# HUB_Sheet1.net
KiCad netlist of a schematic drawn in Altium Designer
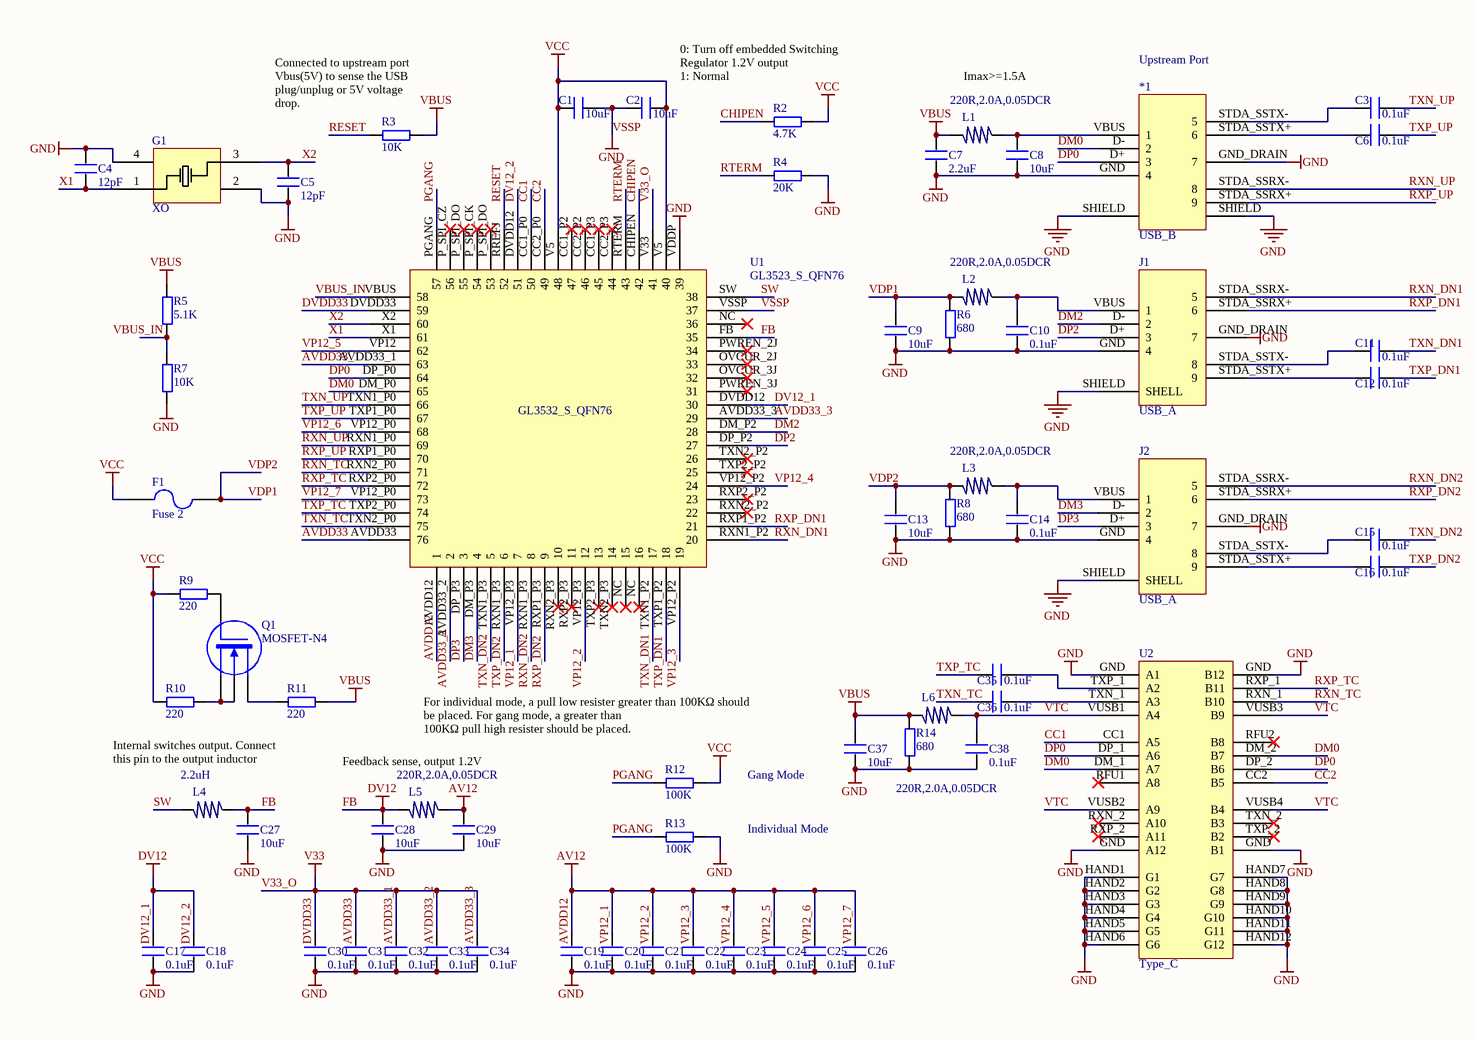
[diagram p0: HUB_Sheet1.SchDoc]

(export (version "E")
  (design (tool "Eeschema 10.0.6"))
  (components
    (comp (ref "*1")
      (value "USB_B")
      (footprint "USB3.0_TP")
      (description "USB3.0_B")
      (libsource (lib "HUB_GL3532") (part "USB_B"))
    )
    (comp (ref "C1") (value "10uF") (footprint "0603P") (libsource (lib "Explorer STM32F407封装库") (part "C")))
    (comp (ref "C2") (value "10uF") (footprint "0603P") (libsource (lib "Explorer STM32F407封装库") (part "C")))
    (comp (ref "C3") (value "0.1uF") (footprint "0603P") (libsource (lib "Explorer STM32F407封装库") (part "C")))
    (comp (ref "C4") (value "12pF") (footprint "0603P") (libsource (lib "Explorer STM32F407封装库") (part "C")))
    (comp (ref "C5") (value "12pF") (footprint "0603P") (libsource (lib "Explorer STM32F407封装库") (part "C")))
    (comp (ref "C6") (value "0.1uF") (footprint "0603P") (libsource (lib "Explorer STM32F407封装库") (part "C")))
    (comp (ref "C7") (value "2.2uF") (footprint "0603P") (libsource (lib "Explorer STM32F407封装库") (part "C")))
    (comp (ref "C8") (value "10uF") (footprint "0603P") (libsource (lib "Explorer STM32F407封装库") (part "C")))
    (comp (ref "C9") (value "10uF") (footprint "0603P") (libsource (lib "Explorer STM32F407封装库") (part "C")))
    (comp (ref "C10")
      (value "0.1uF")
      (footprint "0603P")
      (libsource (lib "Explorer STM32F407封装库") (part "C"))
    )
    (comp (ref "C11")
      (value "0.1uF")
      (footprint "0603P")
      (libsource (lib "Explorer STM32F407封装库") (part "C"))
    )
    (comp (ref "C12")
      (value "0.1uF")
      (footprint "0603P")
      (libsource (lib "Explorer STM32F407封装库") (part "C"))
    )
    (comp (ref "C13") (value "10uF") (footprint "0603P") (libsource (lib "Explorer STM32F407封装库") (part "C")))
    (comp (ref "C14")
      (value "0.1uF")
      (footprint "0603P")
      (libsource (lib "Explorer STM32F407封装库") (part "C"))
    )
    (comp (ref "C15")
      (value "0.1uF")
      (footprint "0603P")
      (libsource (lib "Explorer STM32F407封装库") (part "C"))
    )
    (comp (ref "C16")
      (value "0.1uF")
      (footprint "0603P")
      (libsource (lib "Explorer STM32F407封装库") (part "C"))
    )
    (comp (ref "C17")
      (value "0.1uF")
      (footprint "0603P")
      (libsource (lib "Explorer STM32F407封装库") (part "C"))
    )
    (comp (ref "C18")
      (value "0.1uF")
      (footprint "0603P")
      (libsource (lib "Explorer STM32F407封装库") (part "C"))
    )
    (comp (ref "C19")
      (value "0.1uF")
      (footprint "0603P")
      (libsource (lib "Explorer STM32F407封装库") (part "C"))
    )
    (comp (ref "C20")
      (value "0.1uF")
      (footprint "0603P")
      (libsource (lib "Explorer STM32F407封装库") (part "C"))
    )
    (comp (ref "C21")
      (value "0.1uF")
      (footprint "0603P")
      (libsource (lib "Explorer STM32F407封装库") (part "C"))
    )
    (comp (ref "C22")
      (value "0.1uF")
      (footprint "0603P")
      (libsource (lib "Explorer STM32F407封装库") (part "C"))
    )
    (comp (ref "C23")
      (value "0.1uF")
      (footprint "0603P")
      (libsource (lib "Explorer STM32F407封装库") (part "C"))
    )
    (comp (ref "C24")
      (value "0.1uF")
      (footprint "0603P")
      (libsource (lib "Explorer STM32F407封装库") (part "C"))
    )
    (comp (ref "C25")
      (value "0.1uF")
      (footprint "0603P")
      (libsource (lib "Explorer STM32F407封装库") (part "C"))
    )
    (comp (ref "C26")
      (value "0.1uF")
      (footprint "0603P")
      (libsource (lib "Explorer STM32F407封装库") (part "C"))
    )
    (comp (ref "C27") (value "10uF") (footprint "0603P") (libsource (lib "Explorer STM32F407封装库") (part "C")))
    (comp (ref "C28") (value "10uF") (footprint "0603P") (libsource (lib "Explorer STM32F407封装库") (part "C")))
    (comp (ref "C29") (value "10uF") (footprint "0603P") (libsource (lib "Explorer STM32F407封装库") (part "C")))
    (comp (ref "C30")
      (value "0.1uF")
      (footprint "0603P")
      (libsource (lib "Explorer STM32F407封装库") (part "C"))
    )
    (comp (ref "C31")
      (value "0.1uF")
      (footprint "0603P")
      (libsource (lib "Explorer STM32F407封装库") (part "C"))
    )
    (comp (ref "C32")
      (value "0.1uF")
      (footprint "0603P")
      (libsource (lib "Explorer STM32F407封装库") (part "C"))
    )
    (comp (ref "C33")
      (value "0.1uF")
      (footprint "0603P")
      (libsource (lib "Explorer STM32F407封装库") (part "C"))
    )
    (comp (ref "C34")
      (value "0.1uF")
      (footprint "0603P")
      (libsource (lib "Explorer STM32F407封装库") (part "C"))
    )
    (comp (ref "C35")
      (value "0.1uF")
      (footprint "0603P")
      (libsource (lib "Explorer STM32F407封装库") (part "C"))
    )
    (comp (ref "C36")
      (value "0.1uF")
      (footprint "0603P")
      (libsource (lib "Explorer STM32F407封装库") (part "C"))
    )
    (comp (ref "C37") (value "10uF") (footprint "0603P") (libsource (lib "Explorer STM32F407封装库") (part "C")))
    (comp (ref "C38")
      (value "0.1uF")
      (footprint "0603P")
      (libsource (lib "Explorer STM32F407封装库") (part "C"))
    )
    (comp (ref "F1")
      (value "Fuse 2")
      (footprint "PIN-W2/E2.8")
      (description "Fuse")
      (fields (field (name "PUBLISHER") "Altium Limited"))
      (libsource (lib "Miscellaneous Devices") (part "Fuse 2"))
    )
    (comp (ref "G1")
      (value "XO")
      (footprint "XTAL")
      (description "25M XO")
      (libsource (lib "HUB_GL3532") (part "XO"))
    )
    (comp (ref "J1") (value "USB_A") (description "USB3.0-A") (libsource (lib "GL3532") (part "USB_A")))
    (comp (ref "J2") (value "USB_A") (description "USB3.0-A") (libsource (lib "GL3532") (part "USB_A")))
    (comp (ref "L1")
      (value "220R,2.0A,0.05DCR")
      (footprint "0603P")
      (libsource (lib "Explorer STM32F407封装库") (part "L"))
    )
    (comp (ref "L2")
      (value "220R,2.0A,0.05DCR")
      (footprint "0603P")
      (libsource (lib "Explorer STM32F407封装库") (part "L"))
    )
    (comp (ref "L3")
      (value "220R,2.0A,0.05DCR")
      (footprint "0603P")
      (libsource (lib "Explorer STM32F407封装库") (part "L"))
    )
    (comp (ref "L4") (value "2.2uH") (footprint "0603P") (libsource (lib "Explorer STM32F407封装库") (part "L")))
    (comp (ref "L5")
      (value "220R,2.0A,0.05DCR")
      (footprint "0603P")
      (libsource (lib "Explorer STM32F407封装库") (part "L"))
    )
    (comp (ref "L6")
      (value "220R,2.0A,0.05DCR")
      (footprint "0603P")
      (libsource (lib "Explorer STM32F407封装库") (part "L"))
    )
    (comp (ref "Q1")
      (value "MOSFET-N4")
      (footprint "SOT-343_N")
      (description "N-Channel MOSFET, Externally Terminated Substrate")
      (fields (field (name "PUBLISHER") "Altium Limited"))
      (libsource (lib "Miscellaneous Devices") (part "MOSFET-N4"))
    )
    (comp (ref "R2") (value "4.7K") (footprint "0603P") (libsource (lib "Explorer STM32F407封装库") (part "R")))
    (comp (ref "R3") (value "10K") (footprint "0603P") (libsource (lib "Explorer STM32F407封装库") (part "R")))
    (comp (ref "R4") (value "20K") (footprint "0603P") (libsource (lib "Explorer STM32F407封装库") (part "R")))
    (comp (ref "R5") (value "5.1K") (footprint "0603P") (libsource (lib "Explorer STM32F407封装库") (part "R")))
    (comp (ref "R6") (value "680") (footprint "0603P") (libsource (lib "Explorer STM32F407封装库") (part "R")))
    (comp (ref "R7") (value "10K") (footprint "0603P") (libsource (lib "Explorer STM32F407封装库") (part "R")))
    (comp (ref "R8") (value "680") (footprint "0603P") (libsource (lib "Explorer STM32F407封装库") (part "R")))
    (comp (ref "R9") (value "220") (footprint "0603P") (libsource (lib "Explorer STM32F407封装库") (part "R")))
    (comp (ref "R10") (value "220") (footprint "0603P") (libsource (lib "Explorer STM32F407封装库") (part "R")))
    (comp (ref "R11") (value "220") (footprint "0603P") (libsource (lib "Explorer STM32F407封装库") (part "R")))
    (comp (ref "R12") (value "100K") (footprint "0603P") (libsource (lib "Explorer STM32F407封装库") (part "R")))
    (comp (ref "R13") (value "100K") (footprint "0603P") (libsource (lib "Explorer STM32F407封装库") (part "R")))
    (comp (ref "R14") (value "680") (footprint "0603P") (libsource (lib "Explorer STM32F407封装库") (part "R")))
    (comp (ref "U1") (value "GL3523_S_QFN76") (libsource (lib "GL3532") (part "GL3523_S_QFN76")))
    (comp (ref "U2") (value "Type_C") (libsource (lib "GL3532") (part "Type_C")))
  )
  (nets
    (net (code "1") (name "/AVDD12") (class "Default")
      (node (ref "U1") (pin "AVDD12") (pinfunction "1_AVDD12") (pintype "passive"))
    )
    (net (code "2") (name "/AVDD33") (class "Default")
      (node (ref "U1") (pin "AVDD33") (pinfunction "76_AVDD33") (pintype "passive"))
    )
    (net (code "3") (name "/AVDD33_1") (class "Default")
      (node (ref "U1") (pin "AVDD33_1") (pinfunction "63_AVDD33_1") (pintype "passive"))
    )
    (net (code "5") (name "/AVDD33_3") (class "Default")
      (node (ref "U1") (pin "AVDD33_3") (pinfunction "29_AVDD33_3") (pintype "passive"))
    )
    (net (code "6") (name "/CC1") (class "Default")
      (node (ref "U1") (pin "CC1_P0") (pinfunction "50_CC1_P0") (pintype "passive"))
      (node (ref "U2") (pin "CC1") (pinfunction "A5_CC1") (pintype "passive"))
    )
    (net (code "7") (name "/CC2") (class "Default")
      (node (ref "U1") (pin "CC2_P0") (pinfunction "49_CC2_P0") (pintype "passive"))
      (node (ref "U2") (pin "CC2") (pinfunction "B5_CC2") (pintype "passive"))
    )
    (net (code "8") (name "/CHIPEN") (class "Default")
      (node (ref "R2") (pin "1") (pintype "passive"))
      (node (ref "U1") (pin "CHIPEN") (pinfunction "42_CHIPEN") (pintype "passive"))
    )
    (net (code "9") (name "/DM0") (class "Default")
      (node (ref "*1") (pin "D-") (pinfunction "2_D-") (pintype "passive"))
      (node (ref "U1") (pin "DM_P0") (pinfunction "65_DM_P0") (pintype "passive"))
      (node (ref "U2") (pin "DM_1") (pinfunction "A7_DM_1") (pintype "passive"))
      (node (ref "U2") (pin "DM_2") (pinfunction "B7_DM_2") (pintype "passive"))
    )
    (net (code "10") (name "/DM2") (class "Default")
      (node (ref "J1") (pin "D-") (pinfunction "2_D-") (pintype "passive"))
      (node (ref "U1") (pin "DM_P2") (pinfunction "28_DM_P2") (pintype "passive"))
    )
    (net (code "11") (name "/DM3") (class "Default")
      (node (ref "J2") (pin "D-") (pinfunction "2_D-") (pintype "passive"))
      (node (ref "U1") (pin "DM_P3") (pinfunction "4_DM_P3") (pintype "passive"))
    )
    (net (code "12") (name "/DP0") (class "Default")
      (node (ref "*1") (pin "D+") (pinfunction "3_D+") (pintype "passive"))
      (node (ref "U1") (pin "DP_P0") (pinfunction "64_DP_P0") (pintype "passive"))
      (node (ref "U2") (pin "DP_1") (pinfunction "A6_DP_1") (pintype "passive"))
      (node (ref "U2") (pin "DP_2") (pinfunction "B6_DP_2") (pintype "passive"))
    )
    (net (code "13") (name "/DP2") (class "Default")
      (node (ref "J1") (pin "D+") (pinfunction "3_D+") (pintype "passive"))
      (node (ref "U1") (pin "DP_P2") (pinfunction "27_DP_P2") (pintype "passive"))
    )
    (net (code "14") (name "/DP3") (class "Default")
      (node (ref "J2") (pin "D+") (pinfunction "3_D+") (pintype "passive"))
      (node (ref "U1") (pin "DP_P3") (pinfunction "3_DP_P3") (pintype "passive"))
    )
    (net (code "15") (name "/DV12_1") (class "Default")
      (node (ref "U1") (pin "DVDD12") (pinfunction "30_DVDD12") (pintype "passive"))
    )
    (net (code "16") (name "/DV12_2") (class "Default")
      (node (ref "U1") (pin "DVDD12") (pinfunction "51_DVDD12") (pintype "passive"))
    )
    (net (code "17") (name "/DVDD33") (class "Default")
      (node (ref "U1") (pin "DVDD33") (pinfunction "59_DVDD33") (pintype "passive"))
    )
    (net (code "18") (name "/PGANG") (class "Default")
      (node (ref "R12") (pin "1") (pintype "passive"))
      (node (ref "R13") (pin "1") (pintype "passive"))
      (node (ref "U1") (pin "PGANG") (pinfunction "57_PGANG") (pintype "passive"))
    )
    (net (code "19") (name "/RESET") (class "Default")
      (node (ref "R3") (pin "1") (pintype "passive"))
      (node (ref "U1") (pin "RREFJ") (pinfunction "52_RREFJ") (pintype "passive"))
    )
    (net (code "20") (name "/RTERM") (class "Default")
      (node (ref "R4") (pin "1") (pintype "passive"))
      (node (ref "U1") (pin "RTERM") (pinfunction "43_RTERM") (pintype "passive"))
    )
    (net (code "21") (name "/RXN_DN1") (class "Default")
      (node (ref "J1") (pin "STDA_SSRX-") (pinfunction "5_STDA_SSRX-") (pintype "passive"))
      (node (ref "U1") (pin "RXN1_P2") (pinfunction "20_RXN1_P2") (pintype "passive"))
    )
    (net (code "22") (name "/RXN_DN2") (class "Default")
      (node (ref "J2") (pin "STDA_SSRX-") (pinfunction "5_STDA_SSRX-") (pintype "passive"))
    )
    (net (code "23") (name "/RXN_TC") (class "Default")
      (node (ref "U1") (pin "RXN2_P0") (pinfunction "71_RXN2_P0") (pintype "passive"))
      (node (ref "U2") (pin "RXN_1") (pinfunction "B10_RXN_1") (pintype "passive"))
    )
    (net (code "24") (name "/RXN_UP") (class "Default")
      (node (ref "*1") (pin "STDA_SSRX-") (pinfunction "8_STDA_SSRX-") (pintype "passive"))
      (node (ref "U1") (pin "RXN1_P0") (pinfunction "69_RXN1_P0") (pintype "passive"))
    )
    (net (code "25") (name "/RXP_DN1") (class "Default")
      (node (ref "J1") (pin "STDA_SSRX+") (pinfunction "6_STDA_SSRX+") (pintype "passive"))
      (node (ref "U1") (pin "RXP1_P2") (pinfunction "21_RXP1_P2") (pintype "passive"))
    )
    (net (code "26") (name "/RXP_DN2") (class "Default")
      (node (ref "J2") (pin "STDA_SSRX+") (pinfunction "6_STDA_SSRX+") (pintype "passive"))
    )
    (net (code "27") (name "/RXP_TC") (class "Default")
      (node (ref "U1") (pin "RXP2_P0") (pinfunction "72_RXP2_P0") (pintype "passive"))
      (node (ref "U2") (pin "RXP_1") (pinfunction "B11_RXP_1") (pintype "passive"))
    )
    (net (code "28") (name "/RXP_UP") (class "Default")
      (node (ref "*1") (pin "STDA_SSRX+") (pinfunction "9_STDA_SSRX+") (pintype "passive"))
      (node (ref "U1") (pin "RXP1_P0") (pinfunction "70_RXP1_P0") (pintype "passive"))
    )
    (net (code "29") (name "/SW") (class "Default")
      (node (ref "L4") (pin "2") (pintype "passive"))
      (node (ref "U1") (pin "SW") (pinfunction "38_SW") (pintype "passive"))
    )
    (net (code "30") (name "/TXN_DN1") (class "Default") (node (ref "C11") (pin "2") (pintype "passive")))
    (net (code "31") (name "/TXN_DN2") (class "Default") (node (ref "C15") (pin "2") (pintype "passive")))
    (net (code "32") (name "/TXN_TC") (class "Default")
      (node (ref "C36") (pin "1") (pintype "passive"))
      (node (ref "U1") (pin "TXN2_P0") (pinfunction "75_TXN2_P0") (pintype "passive"))
    )
    (net (code "33") (name "/TXN_UP") (class "Default")
      (node (ref "C3") (pin "2") (pintype "passive"))
      (node (ref "U1") (pin "TXN1_P0") (pinfunction "66_TXN1_P0") (pintype "passive"))
    )
    (net (code "34") (name "/TXP_DN1") (class "Default") (node (ref "C12") (pin "2") (pintype "passive")))
    (net (code "35") (name "/TXP_DN2") (class "Default") (node (ref "C16") (pin "2") (pintype "passive")))
    (net (code "36") (name "/TXP_TC") (class "Default")
      (node (ref "C35") (pin "1") (pintype "passive"))
      (node (ref "U1") (pin "TXP2_P0") (pinfunction "74_TXP2_P0") (pintype "passive"))
    )
    (net (code "37") (name "/TXP_UP") (class "Default")
      (node (ref "C6") (pin "2") (pintype "passive"))
      (node (ref "U1") (pin "TXP1_P0") (pinfunction "67_TXP1_P0") (pintype "passive"))
    )
    (net (code "38") (name "/VBUS_IN") (class "Default")
      (node (ref "U1") (pin "VBUS") (pinfunction "58_VBUS") (pintype "passive"))
    )
    (net (code "39") (name "/VDP1") (class "Default")
      (node (ref "C13") (pin "2") (pintype "passive"))
      (node (ref "C9") (pin "2") (pintype "passive"))
      (node (ref "F1") (pin "2") (pinfunction "2_2") (pintype "passive"))
      (node (ref "L2") (pin "2") (pintype "passive"))
      (node (ref "L3") (pin "2") (pintype "passive"))
      (node (ref "R6") (pin "2") (pintype "passive"))
      (node (ref "R8") (pin "2") (pintype "passive"))
    )
    (net (code "43") (name "/VP12_4") (class "Default")
      (node (ref "U1") (pin "VP12_P2") (pinfunction "24_VP12_P2") (pintype "passive"))
    )
    (net (code "44") (name "/VP12_5") (class "Default")
      (node (ref "U1") (pin "VP12") (pinfunction "62_VP12") (pintype "passive"))
    )
    (net (code "45") (name "/VP12_6") (class "Default")
      (node (ref "U1") (pin "VP12_P0") (pinfunction "68_VP12_P0") (pintype "passive"))
    )
    (net (code "46") (name "/VP12_7") (class "Default")
      (node (ref "U1") (pin "VP12_P0") (pinfunction "73_VP12_P0") (pintype "passive"))
    )
    (net (code "47") (name "/VTC") (class "Default")
      (node (ref "C38") (pin "2") (pintype "passive"))
      (node (ref "L6") (pin "1") (pintype "passive"))
      (node (ref "U2") (pin "VUSB1") (pinfunction "A4_VUSB1") (pintype "passive"))
      (node (ref "U2") (pin "VUSB2") (pinfunction "A9_VUSB2") (pintype "passive"))
      (node (ref "U2") (pin "VUSB3") (pinfunction "B9_VUSB3") (pintype "passive"))
      (node (ref "U2") (pin "VUSB4") (pinfunction "B4_VUSB4") (pintype "passive"))
    )
    (net (code "48") (name "/X1") (class "Default")
      (node (ref "C4") (pin "1") (pintype "passive"))
      (node (ref "G1") (pin "1") (pintype "passive"))
      (node (ref "U1") (pin "X1") (pinfunction "61_X1") (pintype "passive"))
    )
    (net (code "49") (name "/X2") (class "Default")
      (node (ref "C5") (pin "2") (pintype "passive"))
      (node (ref "G1") (pin "3") (pintype "passive"))
      (node (ref "U1") (pin "X2") (pinfunction "60_X2") (pintype "passive"))
    )
    (net (code "50") (name "AV12") (class "Default")
      (node (ref "C19") (pin "2") (pintype "passive"))
      (node (ref "C20") (pin "2") (pintype "passive"))
      (node (ref "C21") (pin "2") (pintype "passive"))
      (node (ref "C22") (pin "2") (pintype "passive"))
      (node (ref "C23") (pin "2") (pintype "passive"))
      (node (ref "C24") (pin "2") (pintype "passive"))
      (node (ref "C25") (pin "2") (pintype "passive"))
      (node (ref "C26") (pin "2") (pintype "passive"))
      (node (ref "C29") (pin "2") (pintype "passive"))
      (node (ref "L5") (pin "1") (pintype "passive"))
    )
    (net (code "51") (name "DV12") (class "Default")
      (node (ref "C17") (pin "2") (pintype "passive"))
      (node (ref "C18") (pin "2") (pintype "passive"))
      (node (ref "C27") (pin "2") (pintype "passive"))
      (node (ref "C28") (pin "2") (pintype "passive"))
      (node (ref "L4") (pin "1") (pintype "passive"))
      (node (ref "L5") (pin "2") (pintype "passive"))
      (node (ref "U1") (pin "FB") (pinfunction "35_FB") (pintype "passive"))
    )
    (net (code "52") (name "GND") (class "Default")
      (node (ref "*1") (pin "GND") (pinfunction "4_GND") (pintype "passive"))
      (node (ref "*1") (pin "GND_DRAIN") (pinfunction "7_GND_DRAIN") (pintype "passive"))
      (node (ref "*1") (pin "SHIELD") (pintype "passive"))
      (node (ref "C1") (pin "2") (pintype "passive"))
      (node (ref "C10") (pin "1") (pintype "passive"))
      (node (ref "C13") (pin "1") (pintype "passive"))
      (node (ref "C14") (pin "1") (pintype "passive"))
      (node (ref "C17") (pin "1") (pintype "passive"))
      (node (ref "C18") (pin "1") (pintype "passive"))
      (node (ref "C19") (pin "1") (pintype "passive"))
      (node (ref "C2") (pin "1") (pintype "passive"))
      (node (ref "C20") (pin "1") (pintype "passive"))
      (node (ref "C21") (pin "1") (pintype "passive"))
      (node (ref "C22") (pin "1") (pintype "passive"))
      (node (ref "C23") (pin "1") (pintype "passive"))
      (node (ref "C24") (pin "1") (pintype "passive"))
      (node (ref "C25") (pin "1") (pintype "passive"))
      (node (ref "C26") (pin "1") (pintype "passive"))
      (node (ref "C27") (pin "1") (pintype "passive"))
      (node (ref "C28") (pin "1") (pintype "passive"))
      (node (ref "C29") (pin "1") (pintype "passive"))
      (node (ref "C30") (pin "1") (pintype "passive"))
      (node (ref "C31") (pin "1") (pintype "passive"))
      (node (ref "C32") (pin "1") (pintype "passive"))
      (node (ref "C33") (pin "1") (pintype "passive"))
      (node (ref "C34") (pin "1") (pintype "passive"))
      (node (ref "C37") (pin "1") (pintype "passive"))
      (node (ref "C38") (pin "1") (pintype "passive"))
      (node (ref "C4") (pin "2") (pintype "passive"))
      (node (ref "C5") (pin "1") (pintype "passive"))
      (node (ref "C7") (pin "1") (pintype "passive"))
      (node (ref "C8") (pin "1") (pintype "passive"))
      (node (ref "C9") (pin "1") (pintype "passive"))
      (node (ref "G1") (pin "2") (pintype "passive"))
      (node (ref "G1") (pin "4") (pintype "passive"))
      (node (ref "J1") (pin "GND") (pinfunction "4_GND") (pintype "passive"))
      (node (ref "J1") (pin "GND_DRAIN") (pinfunction "7_GND_DRAIN") (pintype "passive"))
      (node (ref "J1") (pin "SHIELD") (pinfunction "SHELL_SHIELD") (pintype "passive"))
      (node (ref "J2") (pin "GND") (pinfunction "4_GND") (pintype "passive"))
      (node (ref "J2") (pin "GND_DRAIN") (pinfunction "7_GND_DRAIN") (pintype "passive"))
      (node (ref "J2") (pin "SHIELD") (pinfunction "SHELL_SHIELD") (pintype "passive"))
      (node (ref "R13") (pin "2") (pintype "passive"))
      (node (ref "R14") (pin "1") (pintype "passive"))
      (node (ref "R4") (pin "2") (pintype "passive"))
      (node (ref "R6") (pin "1") (pintype "passive"))
      (node (ref "R7") (pin "1") (pintype "passive"))
      (node (ref "R8") (pin "1") (pintype "passive"))
      (node (ref "U1") (pin "VDDP") (pinfunction "39_VDDP") (pintype "passive"))
      (node (ref "U1") (pin "VSSP") (pinfunction "37_VSSP") (pintype "passive"))
      (node (ref "U2") (pin "GND") (pinfunction "B12_GND") (pintype "passive"))
      (node (ref "U2") (pin "HAND1") (pinfunction "G1_HAND1") (pintype "passive"))
      (node (ref "U2") (pin "HAND10") (pinfunction "G10_HAND10") (pintype "passive"))
      (node (ref "U2") (pin "HAND11") (pinfunction "G11_HAND11") (pintype "passive"))
      (node (ref "U2") (pin "HAND12") (pinfunction "G12_HAND12") (pintype "passive"))
      (node (ref "U2") (pin "HAND2") (pinfunction "G2_HAND2") (pintype "passive"))
      (node (ref "U2") (pin "HAND3") (pinfunction "G3_HAND3") (pintype "passive"))
      (node (ref "U2") (pin "HAND4") (pinfunction "G4_HAND4") (pintype "passive"))
      (node (ref "U2") (pin "HAND5") (pinfunction "G5_HAND5") (pintype "passive"))
      (node (ref "U2") (pin "HAND6") (pinfunction "G6_HAND6") (pintype "passive"))
      (node (ref "U2") (pin "HAND7") (pinfunction "G7_HAND7") (pintype "passive"))
      (node (ref "U2") (pin "HAND8") (pinfunction "G8_HAND8") (pintype "passive"))
      (node (ref "U2") (pin "HAND9") (pinfunction "G9_HAND9") (pintype "passive"))
    )
    (net (code "53") (name "Net-(*1-1)") (class "Default")
      (node (ref "*1") (pin "VBUS") (pinfunction "1_VBUS") (pintype "passive"))
      (node (ref "C8") (pin "2") (pintype "passive"))
      (node (ref "L1") (pin "1") (pintype "passive"))
    )
    (net (code "54") (name "Net-(*1-5)") (class "Default")
      (node (ref "*1") (pin "STDA_SSTX-") (pinfunction "5_STDA_SSTX-") (pintype "passive"))
      (node (ref "C3") (pin "1") (pintype "passive"))
    )
    (net (code "55") (name "Net-(*1-6)") (class "Default")
      (node (ref "*1") (pin "STDA_SSTX+") (pinfunction "6_STDA_SSTX+") (pintype "passive"))
      (node (ref "C6") (pin "1") (pintype "passive"))
    )
    (net (code "56") (name "Net-(J1-1)") (class "Default")
      (node (ref "C10") (pin "2") (pintype "passive"))
      (node (ref "J1") (pin "VBUS") (pinfunction "1_VBUS") (pintype "passive"))
      (node (ref "L2") (pin "1") (pintype "passive"))
    )
    (net (code "57") (name "Net-(J1-8)") (class "Default")
      (node (ref "C11") (pin "1") (pintype "passive"))
      (node (ref "J1") (pin "STDA_SSTX-") (pinfunction "8_STDA_SSTX-") (pintype "passive"))
    )
    (net (code "58") (name "Net-(J1-9)") (class "Default")
      (node (ref "C12") (pin "1") (pintype "passive"))
      (node (ref "J1") (pin "STDA_SSTX+") (pinfunction "9_STDA_SSTX+") (pintype "passive"))
    )
    (net (code "59") (name "Net-(J2-1)") (class "Default")
      (node (ref "C14") (pin "2") (pintype "passive"))
      (node (ref "J2") (pin "VBUS") (pinfunction "1_VBUS") (pintype "passive"))
      (node (ref "L3") (pin "1") (pintype "passive"))
    )
    (net (code "60") (name "Net-(J2-8)") (class "Default")
      (node (ref "C15") (pin "1") (pintype "passive"))
      (node (ref "J2") (pin "STDA_SSTX-") (pinfunction "8_STDA_SSTX-") (pintype "passive"))
    )
    (net (code "61") (name "Net-(J2-9)") (class "Default")
      (node (ref "C16") (pin "1") (pintype "passive"))
      (node (ref "J2") (pin "STDA_SSTX+") (pinfunction "9_STDA_SSTX+") (pintype "passive"))
    )
    (net (code "62") (name "Net-(Q1-D)") (class "Default")
      (node (ref "Q1") (pin "2") (pinfunction "D_2") (pintype "passive"))
      (node (ref "R11") (pin "1") (pintype "passive"))
    )
    (net (code "63") (name "Net-(Q1-G)") (class "Default")
      (node (ref "Q1") (pin "1") (pinfunction "G_1") (pintype "passive"))
      (node (ref "R9") (pin "2") (pintype "passive"))
    )
    (net (code "64") (name "Net-(Q1-S)") (class "Default")
      (node (ref "Q1") (pin "3") (pinfunction "U_3") (pintype "passive"))
      (node (ref "Q1") (pin "4") (pinfunction "S_4") (pintype "passive"))
      (node (ref "R10") (pin "2") (pintype "passive"))
    )
    (net (code "65") (name "Net-(R5-Pad1)") (class "Default")
      (node (ref "R5") (pin "1") (pintype "passive"))
      (node (ref "R7") (pin "2") (pintype "passive"))
    )
    (net (code "66") (name "Net-(U2-A2)") (class "Default")
      (node (ref "C35") (pin "2") (pintype "passive"))
      (node (ref "U2") (pin "TXP_1") (pinfunction "A2_TXP_1") (pintype "passive"))
    )
    (net (code "67") (name "Net-(U2-A3)") (class "Default")
      (node (ref "C36") (pin "2") (pintype "passive"))
      (node (ref "U2") (pin "TXN_1") (pinfunction "A3_TXN_1") (pintype "passive"))
    )
    (net (code "68") (name "V33") (class "Default")
      (node (ref "C30") (pin "2") (pintype "passive"))
      (node (ref "C31") (pin "2") (pintype "passive"))
      (node (ref "C32") (pin "2") (pintype "passive"))
      (node (ref "C33") (pin "2") (pintype "passive"))
      (node (ref "C34") (pin "2") (pintype "passive"))
      (node (ref "U1") (pin "V33") (pinfunction "41_V33") (pintype "passive"))
    )
    (net (code "69") (name "VBUS") (class "Default")
      (node (ref "C37") (pin "2") (pintype "passive"))
      (node (ref "C7") (pin "2") (pintype "passive"))
      (node (ref "L1") (pin "2") (pintype "passive"))
      (node (ref "L6") (pin "2") (pintype "passive"))
      (node (ref "R11") (pin "2") (pintype "passive"))
      (node (ref "R14") (pin "2") (pintype "passive"))
      (node (ref "R3") (pin "2") (pintype "passive"))
      (node (ref "R5") (pin "2") (pintype "passive"))
    )
    (net (code "70") (name "VCC") (class "Default")
      (node (ref "C1") (pin "1") (pintype "passive"))
      (node (ref "C2") (pin "2") (pintype "passive"))
      (node (ref "F1") (pin "1") (pinfunction "1_1") (pintype "passive"))
      (node (ref "R10") (pin "1") (pintype "passive"))
      (node (ref "R12") (pin "2") (pintype "passive"))
      (node (ref "R2") (pin "2") (pintype "passive"))
      (node (ref "R9") (pin "1") (pintype "passive"))
      (node (ref "U1") (pin "V5") (pinfunction "48_V5") (pintype "passive"))
    )
    (net (code "71") (name "unconnected-(U1-2-PadAVDD33_2)") (class "Default")
      (node (ref "U1") (pin "AVDD33_2") (pinfunction "2_AVDD33_2") (pintype "passive"))
    )
    (net (code "72") (name "unconnected-(U1-5-PadTXN1_P3)") (class "Default")
      (node (ref "U1") (pin "TXN1_P3") (pinfunction "5_TXN1_P3") (pintype "passive"))
    )
    (net (code "73") (name "unconnected-(U1-6-PadRXN1_P3)") (class "Default")
      (node (ref "U1") (pin "RXN1_P3") (pinfunction "6_RXN1_P3") (pintype "passive"))
    )
    (net (code "74") (name "unconnected-(U1-7-PadVP12_P3)") (class "Default")
      (node (ref "U1") (pin "VP12_P3") (pinfunction "7_VP12_P3") (pintype "passive"))
    )
    (net (code "75") (name "unconnected-(U1-8-PadRXN1_P3)") (class "Default")
      (node (ref "U1") (pin "RXN1_P3") (pinfunction "8_RXN1_P3") (pintype "passive"))
    )
    (net (code "76") (name "unconnected-(U1-9-PadRXP1_P3)") (class "Default")
      (node (ref "U1") (pin "RXP1_P3") (pinfunction "9_RXP1_P3") (pintype "passive"))
    )
    (net (code "77") (name "unconnected-(U1-10-PadRXN2_P3)") (class "Default")
      (node (ref "U1") (pin "RXN2_P3") (pinfunction "10_RXN2_P3") (pintype "passive+no_connect"))
    )
    (net (code "78") (name "unconnected-(U1-11-PadRXP2_P3)") (class "Default")
      (node (ref "U1") (pin "RXP2_P3") (pinfunction "11_RXP2_P3") (pintype "passive+no_connect"))
    )
    (net (code "79") (name "unconnected-(U1-12-PadVP12_P3)") (class "Default")
      (node (ref "U1") (pin "VP12_P3") (pinfunction "12_VP12_P3") (pintype "passive"))
    )
    (net (code "80") (name "unconnected-(U1-13-PadTXP2_P3)") (class "Default")
      (node (ref "U1") (pin "TXP2_P3") (pinfunction "13_TXP2_P3") (pintype "passive+no_connect"))
    )
    (net (code "81") (name "unconnected-(U1-14-PadTXN2_P3)") (class "Default")
      (node (ref "U1") (pin "TXN2_P3") (pinfunction "14_TXN2_P3") (pintype "passive+no_connect"))
    )
    (net (code "82") (name "unconnected-(U1-15-PadNC)") (class "Default")
      (node (ref "U1") (pin "NC") (pinfunction "15_NC") (pintype "passive+no_connect"))
    )
    (net (code "83") (name "unconnected-(U1-16-PadNC)") (class "Default")
      (node (ref "U1") (pin "NC") (pinfunction "16_NC") (pintype "passive+no_connect"))
    )
    (net (code "84") (name "unconnected-(U1-17-PadTXN1_P2)") (class "Default")
      (node (ref "U1") (pin "TXN1_P2") (pinfunction "17_TXN1_P2") (pintype "passive"))
    )
    (net (code "85") (name "unconnected-(U1-18-PadTXP1_P2)") (class "Default")
      (node (ref "U1") (pin "TXP1_P2") (pinfunction "18_TXP1_P2") (pintype "passive"))
    )
    (net (code "86") (name "unconnected-(U1-19-PadVP12_P2)") (class "Default")
      (node (ref "U1") (pin "VP12_P2") (pinfunction "19_VP12_P2") (pintype "passive"))
    )
    (net (code "87") (name "unconnected-(U1-22-PadRXN2_P2)") (class "Default")
      (node (ref "U1") (pin "RXN2_P2") (pinfunction "22_RXN2_P2") (pintype "passive+no_connect"))
    )
    (net (code "88") (name "unconnected-(U1-23-PadRXP2_P2)") (class "Default")
      (node (ref "U1") (pin "RXP2_P2") (pinfunction "23_RXP2_P2") (pintype "passive+no_connect"))
    )
    (net (code "89") (name "unconnected-(U1-25-PadTXP2_P2)") (class "Default")
      (node (ref "U1") (pin "TXP2_P2") (pinfunction "25_TXP2_P2") (pintype "passive+no_connect"))
    )
    (net (code "90") (name "unconnected-(U1-26-PadTXN2_P2)") (class "Default")
      (node (ref "U1") (pin "TXN2_P2") (pinfunction "26_TXN2_P2") (pintype "passive+no_connect"))
    )
    (net (code "91") (name "unconnected-(U1-31-PadPWREN_3J)") (class "Default")
      (node (ref "U1") (pin "PWREN_3J") (pinfunction "31_PWREN_3J") (pintype "passive+no_connect"))
    )
    (net (code "92") (name "unconnected-(U1-32-PadOVCUR_3J)") (class "Default")
      (node (ref "U1") (pin "OVCUR_3J") (pinfunction "32_OVCUR_3J") (pintype "passive+no_connect"))
    )
    (net (code "93") (name "unconnected-(U1-33-PadOVCUR_2J)") (class "Default")
      (node (ref "U1") (pin "OVCUR_2J") (pinfunction "33_OVCUR_2J") (pintype "passive+no_connect"))
    )
    (net (code "94") (name "unconnected-(U1-34-PadPWREN_2J)") (class "Default")
      (node (ref "U1") (pin "PWREN_2J") (pinfunction "34_PWREN_2J") (pintype "passive+no_connect"))
    )
    (net (code "95") (name "unconnected-(U1-36-PadNC)") (class "Default")
      (node (ref "U1") (pin "NC") (pinfunction "36_NC") (pintype "passive+no_connect"))
    )
    (net (code "96") (name "unconnected-(U1-44-PadCC2_P3)") (class "Default")
      (node (ref "U1") (pin "CC2_P3") (pinfunction "44_CC2_P3") (pintype "passive+no_connect"))
    )
    (net (code "97") (name "unconnected-(U1-45-PadCC1_P3)") (class "Default")
      (node (ref "U1") (pin "CC1_P3") (pinfunction "45_CC1_P3") (pintype "passive+no_connect"))
    )
    (net (code "98") (name "unconnected-(U1-46-PadCC2_P2)") (class "Default")
      (node (ref "U1") (pin "CC2_P2") (pinfunction "46_CC2_P2") (pintype "passive+no_connect"))
    )
    (net (code "99") (name "unconnected-(U1-47-PadCC1_P2)") (class "Default")
      (node (ref "U1") (pin "CC1_P2") (pinfunction "47_CC1_P2") (pintype "passive+no_connect"))
    )
    (net (code "100") (name "unconnected-(U1-53-PadP_SPI_DO)") (class "Default")
      (node (ref "U1") (pin "P_SPI_DO") (pinfunction "53_P_SPI_DO") (pintype "passive+no_connect"))
    )
    (net (code "101") (name "unconnected-(U1-54-PadP_SPI_CK)") (class "Default")
      (node (ref "U1") (pin "P_SPI_CK") (pinfunction "54_P_SPI_CK") (pintype "passive+no_connect"))
    )
    (net (code "102") (name "unconnected-(U1-55-PadP_SPI_DO)") (class "Default")
      (node (ref "U1") (pin "P_SPI_DO") (pinfunction "55_P_SPI_DO") (pintype "passive+no_connect"))
    )
    (net (code "103") (name "unconnected-(U1-56-PadP_SPI_CZ)") (class "Default")
      (node (ref "U1") (pin "P_SPI_CZ") (pinfunction "56_P_SPI_CZ") (pintype "passive+no_connect"))
    )
    (net (code "104") (name "unconnected-(U2-A8-PadRFU1)") (class "Default")
      (node (ref "U2") (pin "RFU1") (pinfunction "A8_RFU1") (pintype "passive+no_connect"))
    )
    (net (code "105") (name "unconnected-(U2-A10-PadRXN_2)") (class "Default")
      (node (ref "U2") (pin "RXN_2") (pinfunction "A10_RXN_2") (pintype "passive+no_connect"))
    )
    (net (code "106") (name "unconnected-(U2-A11-PadRXP_2)") (class "Default")
      (node (ref "U2") (pin "RXP_2") (pinfunction "A11_RXP_2") (pintype "passive+no_connect"))
    )
    (net (code "107") (name "unconnected-(U2-B2-PadTXP_2)") (class "Default")
      (node (ref "U2") (pin "TXP_2") (pinfunction "B2_TXP_2") (pintype "passive+no_connect"))
    )
    (net (code "108") (name "unconnected-(U2-B3-PadTXN_2)") (class "Default")
      (node (ref "U2") (pin "TXN_2") (pinfunction "B3_TXN_2") (pintype "passive+no_connect"))
    )
    (net (code "109") (name "unconnected-(U2-B8-PadRFU2)") (class "Default")
      (node (ref "U2") (pin "RFU2") (pinfunction "B8_RFU2") (pintype "passive+no_connect"))
    )
  )
)
